# NEO9M.net
KiCad netlist of a schematic drawn in Altium Designer
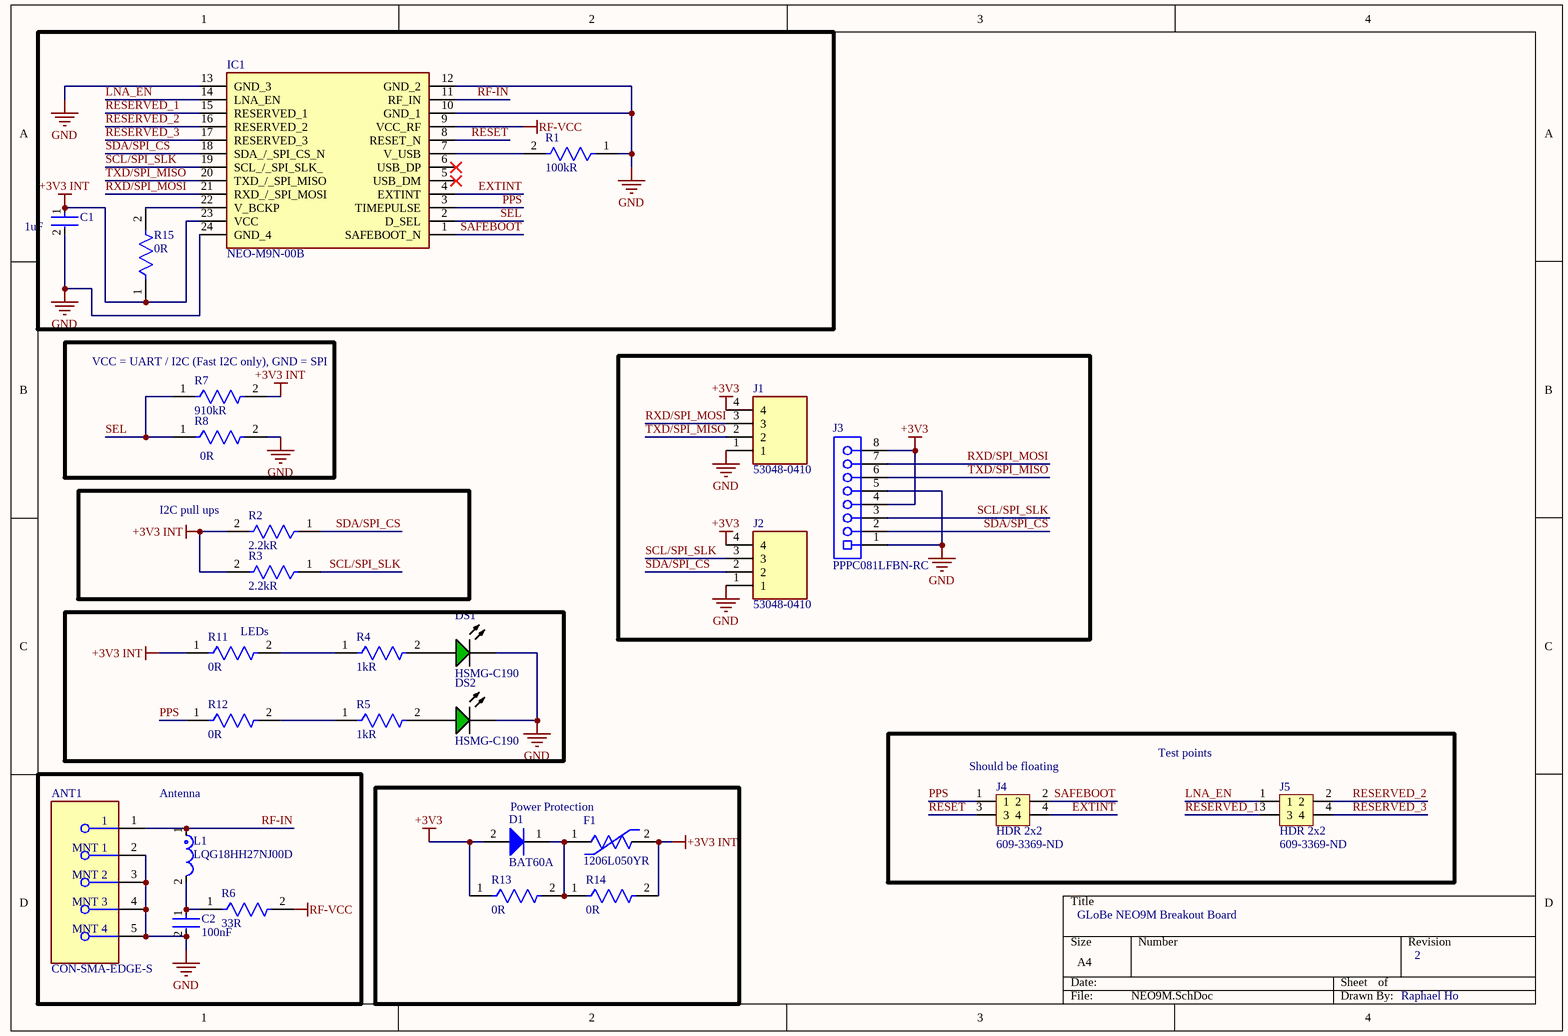
[diagram p0: NEO9M.SchDoc]

(export (version "E")
  (design (tool "Eeschema 10.0.6"))
  (components
    (comp (ref "ANT1")
      (value "CON-SMA-EDGE-S")
      (footprint "FP-CON-SMA-EDGE-S-MFG")
      (description "CONN SMA JACK STR EDGE MNT")
      (fields
        (field (name "OCTOPART") "https://octopart.com/con-sma-edge-s-rf+solutions-70967450")
        (field (name "MANUFACTURER") "RF Solutions Ltd.")
      )
      (libsource (lib "Altium Content Vault") (part "a163d97a771fcdd2fd1f1a9264c171f"))
    )
    (comp (ref "C1")
      (value "1uF")
      (footprint "FP-GCM188-0_1-IPC_B")
      (description "Ceramic Capacitor for Automotive 1uF  ±10% 16VDC X7R 0603 Paper T/R")
      (fields (field (name "VOLTAGE") "16V") (field (name "TOLERANCE") "10%"))
      (libsource (lib "Altium Content Vault") (part "02cd4be3c70576c341d710602a673aa"))
    )
    (comp (ref "C2")
      (value "100nF")
      (footprint "FP-GCM188-0_1-IPC_A")
      (description "CAP CER 0.1UF 50V X7R 0603")
      (fields (field (name "TOLERANCE") "10%"))
      (libsource (lib "Altium Content Vault") (part "b4654b650e69147ec39a6b967a45e02"))
    )
    (comp (ref "D1")
      (value "BAT60A")
      (footprint "INF-SOD323_V")
      (description "Silicon Schottky Diode, -55 to 85 degC, SOD323, Reel, Green")
      (fields (field (name "MANUFACTURER") "Infineon"))
      (libsource (lib "Altium Content Vault") (part "INF-D_K1A2-2"))
    )
    (comp (ref "DS1")
      (value "HSMG-C190")
      (footprint "AVAG-HSMX-C190_V")
      (description "Chip LED, Green, 2.2 V, -40 to 85 degC, 2-Pin SMD, RoHS, Tape and Reel")
      (libsource (lib "Altium Content Vault") (part "LED-GREEN-AK-2"))
    )
    (comp (ref "DS2")
      (value "HSMG-C190")
      (footprint "AVAG-HSMX-C190_V")
      (description "Chip LED, Green, 2.2 V, -40 to 85 degC, 2-Pin SMD, RoHS, Tape and Reel")
      (libsource (lib "Altium Content Vault") (part "LED-GREEN-AK-2"))
    )
    (comp (ref "F1")
      (value "1206L050YR")
      (footprint "FP-1206L050YR-MFG")
      (description "PTC RESET FUSE 6V 500MA 1206")
      (libsource (lib "Altium Content Vault") (part "fdf083d5f6389a9a1c4e51137f46658"))
    )
    (comp (ref "IC1")
      (value "NEO-M9N-00B")
      (footprint "SamacSys:NEOM9N00B")
      (description "Integrated Circuit")
      (fields (field (name "MOUSER PART NUMBER") "377-NEO-M9N-00B"))
      (libsource (lib "*") (part "NEO-M9N-00B"))
    )
    (comp (ref "J1")
      (value "53048-0410")
      (footprint "SamacSys:530480410")
      (description "Connector")
      (fields (field (name "MOUSER PART NUMBER") "538-53048-0410"))
      (libsource (lib "*") (part "53048-0410"))
    )
    (comp (ref "J2")
      (value "53048-0410")
      (footprint "SamacSys:530480410")
      (description "Connector")
      (fields (field (name "MOUSER PART NUMBER") "538-53048-0410"))
      (libsource (lib "*") (part "53048-0410"))
    )
    (comp (ref "J3")
      (value "PPPC081LFBN-RC")
      (footprint "SLIN-PPPC081LFBN-RC_V")
      (fields (field (name "MANUFACTURER") "Sullins"))
      (libsource (lib "CubeSat Team") (part "CN-1P-F-R8"))
    )
    (comp (ref "J4")
      (value "HDR 2x2")
      (footprint "HDR_2x2_2.54mm")
      (description "CONN HEADER VERT 4POS 2.54MM")
      (fields
        (field (name "MANUFACTURER") "Amphenol FCI")
        (field (name "MANUFACTURER PART NUMBER") "68602-204HLF")
        (field (name "SUPPLIER PART NUMBER 1") "609-3369-ND")
      )
      (libsource (lib "Male_Header_2x2_2.54mm") (part "68602-204HLF"))
    )
    (comp (ref "J5")
      (value "HDR 2x2")
      (footprint "HDR_2x2_2.54mm")
      (description "CONN HEADER VERT 4POS 2.54MM")
      (fields
        (field (name "MANUFACTURER") "Amphenol FCI")
        (field (name "MANUFACTURER PART NUMBER") "68602-204HLF")
        (field (name "SUPPLIER PART NUMBER 1") "609-3369-ND")
      )
      (libsource (lib "Male_Header_2x2_2.54mm") (part "68602-204HLF"))
    )
    (comp (ref "L1")
      (value "LQG18HH27NJ00D")
      (footprint "FP-LQG18HH_00-IPC_C")
      (description "Multilayer type Inductor for Automotive 27nH ±5% 0.54Ω 500mA 0603")
      (libsource (lib "Altium Content Vault") (part "4cc4b267dca4c8e51f7102f422741d8"))
    )
    (comp (ref "R1")
      (value "100kR")
      (footprint "FP-AC0603-MFG")
      (description "RES 100kΩ 5.00% 0.1W 0603")
      (fields (field (name "TOLERANCE") "5%"))
      (libsource (lib "Altium Content Vault") (part "1029c3af85768c4190bb7ad29bc67b5"))
    )
    (comp (ref "R2")
      (value "2.2kR")
      (footprint "FP-AC0603-IPC_B")
      (description "RES 2.2kΩ 5.00% 0.1W 0603")
      (fields (field (name "TOLERANCE") "5%"))
      (libsource (lib "Altium Content Vault") (part "1029c3af85768c4190bb7ad29bc67b5"))
    )
    (comp (ref "R3")
      (value "2.2kR")
      (footprint "FP-AC0603-IPC_B")
      (description "RES 2.2kΩ 5.00% 0.1W 0603")
      (fields (field (name "TOLERANCE") "5%"))
      (libsource (lib "Altium Content Vault") (part "1029c3af85768c4190bb7ad29bc67b5"))
    )
    (comp (ref "R4")
      (value "1kR")
      (footprint "FP-AC0603-IPC_A")
      (description "RES 1kΩ 1.00% 0.1W 0603")
      (fields (field (name "TOLERANCE") "1%"))
      (libsource (lib "Altium Content Vault") (part "1029c3af85768c4190bb7ad29bc67b5"))
    )
    (comp (ref "R5")
      (value "1kR")
      (footprint "FP-AC0603-IPC_A")
      (description "RES 1kΩ 1.00% 0.1W 0603")
      (fields (field (name "TOLERANCE") "1%"))
      (libsource (lib "Altium Content Vault") (part "1029c3af85768c4190bb7ad29bc67b5"))
    )
    (comp (ref "R6")
      (value "33R")
      (footprint "FP-AC0603-IPC_C")
      (description "RES 33Ω 0.50% 0.1W 0603")
      (libsource (lib "Altium Content Vault") (part "1029c3af85768c4190bb7ad29bc67b5"))
    )
    (comp (ref "R7")
      (value "910kR")
      (footprint "FP-AC0603-IPC_B")
      (description "RES 910KΩ 1.00% 0.1W 0603")
      (fields (field (name "TOLERANCE") "1%"))
      (libsource (lib "Altium Content Vault") (part "1029c3af85768c4190bb7ad29bc67b5"))
    )
    (comp (ref "R8")
      (value "0R")
      (footprint "FP-AC0603-IPC_A")
      (description "RES 0Ω 0.00% 0.1W 0603")
      (fields (field (name "TOLERANCE") "5%"))
      (libsource (lib "Altium Content Vault") (part "1029c3af85768c4190bb7ad29bc67b5"))
    )
    (comp (ref "R11")
      (value "0R")
      (footprint "FP-AC0603-IPC_A")
      (description "RES 0Ω 0.00% 0.1W 0603")
      (fields (field (name "TOLERANCE") "5%"))
      (libsource (lib "Altium Content Vault") (part "1029c3af85768c4190bb7ad29bc67b5"))
    )
    (comp (ref "R12")
      (value "0R")
      (footprint "FP-AC0603-IPC_A")
      (description "RES 0Ω 0.00% 0.1W 0603")
      (fields (field (name "TOLERANCE") "5%"))
      (libsource (lib "Altium Content Vault") (part "1029c3af85768c4190bb7ad29bc67b5"))
    )
    (comp (ref "R13")
      (value "0R")
      (footprint "FP-AC0603-IPC_A")
      (description "RES 0Ω 0.00% 0.1W 0603")
      (fields (field (name "TOLERANCE") "5%"))
      (libsource (lib "Altium Content Vault") (part "1029c3af85768c4190bb7ad29bc67b5"))
    )
    (comp (ref "R14")
      (value "0R")
      (footprint "FP-AC0603-IPC_A")
      (description "RES 0Ω 0.00% 0.1W 0603")
      (fields (field (name "TOLERANCE") "5%"))
      (libsource (lib "Altium Content Vault") (part "1029c3af85768c4190bb7ad29bc67b5"))
    )
    (comp (ref "R15")
      (value "0R")
      (footprint "FP-AC0603-IPC_A")
      (description "RES 0Ω 0.00% 0.1W 0603")
      (fields (field (name "TOLERANCE") "5%"))
      (libsource (lib "Altium Content Vault") (part "1029c3af85768c4190bb7ad29bc67b5"))
    )
  )
  (nets
    (net (code "1") (name "+3V3") (class "Default")
      (node (ref "D1") (pin "2") (pinfunction "A_2") (pintype "passive"))
      (node (ref "J1") (pin "4") (pinfunction "4_4") (pintype "passive"))
      (node (ref "J2") (pin "4") (pinfunction "4_4") (pintype "passive"))
      (node (ref "J3") (pin "4") (pinfunction "4_4") (pintype "passive"))
      (node (ref "J3") (pin "8") (pinfunction "8_8") (pintype "passive"))
      (node (ref "R13") (pin "1") (pinfunction "1_1") (pintype "passive"))
    )
    (net (code "2") (name "+3V3 INT") (class "Default")
      (node (ref "C1") (pin "1") (pinfunction "1_1") (pintype "passive"))
      (node (ref "F1") (pin "2") (pinfunction "2_2") (pintype "passive"))
      (node (ref "IC1") (pin "23") (pinfunction "VCC_23") (pintype "passive"))
      (node (ref "R11") (pin "1") (pinfunction "1_1") (pintype "passive"))
      (node (ref "R14") (pin "2") (pinfunction "2_2") (pintype "passive"))
      (node (ref "R15") (pin "1") (pinfunction "1_1") (pintype "passive"))
      (node (ref "R2") (pin "2") (pinfunction "2_2") (pintype "passive"))
      (node (ref "R3") (pin "2") (pinfunction "2_2") (pintype "passive"))
      (node (ref "R7") (pin "2") (pinfunction "2_2") (pintype "passive"))
    )
    (net (code "3") (name "/EXTINT") (class "Default")
      (node (ref "IC1") (pin "4") (pinfunction "EXTINT_4") (pintype "passive"))
      (node (ref "J4") (pin "4") (pinfunction "4_4") (pintype "passive"))
    )
    (net (code "4") (name "/LNA_EN") (class "Default")
      (node (ref "IC1") (pin "14") (pinfunction "LNA_EN_14") (pintype "passive"))
      (node (ref "J5") (pin "1") (pinfunction "1_1") (pintype "passive"))
    )
    (net (code "5") (name "/PPS") (class "Default")
      (node (ref "IC1") (pin "3") (pinfunction "TIMEPULSE_3") (pintype "passive"))
      (node (ref "J4") (pin "1") (pinfunction "1_1") (pintype "passive"))
      (node (ref "R12") (pin "1") (pinfunction "1_1") (pintype "passive"))
    )
    (net (code "6") (name "/RESERVED_1") (class "Default")
      (node (ref "IC1") (pin "15") (pinfunction "RESERVED_1_15") (pintype "passive"))
      (node (ref "J5") (pin "3") (pinfunction "3_3") (pintype "passive"))
    )
    (net (code "7") (name "/RESERVED_2") (class "Default")
      (node (ref "IC1") (pin "16") (pinfunction "RESERVED_2_16") (pintype "passive"))
      (node (ref "J5") (pin "2") (pinfunction "2_2") (pintype "passive"))
    )
    (net (code "8") (name "/RESERVED_3") (class "Default")
      (node (ref "IC1") (pin "17") (pinfunction "RESERVED_3_17") (pintype "passive"))
      (node (ref "J5") (pin "4") (pinfunction "4_4") (pintype "passive"))
    )
    (net (code "9") (name "/RESET") (class "Default")
      (node (ref "IC1") (pin "8") (pinfunction "RESET_N_8") (pintype "passive"))
      (node (ref "J4") (pin "3") (pinfunction "3_3") (pintype "passive"))
    )
    (net (code "10") (name "/RF-IN") (class "Default")
      (node (ref "ANT1") (pin "1") (pinfunction "1_1") (pintype "passive"))
      (node (ref "IC1") (pin "11") (pinfunction "RF_IN_11") (pintype "passive"))
      (node (ref "L1") (pin "1") (pinfunction "1_1") (pintype "passive"))
    )
    (net (code "11") (name "/RXD{slash}SPI_MOSI") (class "Default")
      (node (ref "IC1") (pin "21") (pinfunction "RXD_/_SPI_MOSI_21") (pintype "passive"))
      (node (ref "J1") (pin "3") (pinfunction "3_3") (pintype "passive"))
      (node (ref "J3") (pin "7") (pinfunction "7_7") (pintype "passive"))
    )
    (net (code "12") (name "/SAFEBOOT") (class "Default")
      (node (ref "IC1") (pin "1") (pinfunction "SAFEBOOT_N_1") (pintype "passive"))
      (node (ref "J4") (pin "2") (pinfunction "2_2") (pintype "passive"))
    )
    (net (code "13") (name "/SCL{slash}SPI_SLK") (class "Default")
      (node (ref "IC1") (pin "19") (pinfunction "SCL_/_SPI_SLK__19") (pintype "passive"))
      (node (ref "J2") (pin "3") (pinfunction "3_3") (pintype "passive"))
      (node (ref "J3") (pin "3") (pinfunction "3_3") (pintype "passive"))
      (node (ref "R3") (pin "1") (pinfunction "1_1") (pintype "passive"))
    )
    (net (code "14") (name "/SDA{slash}SPI_CS") (class "Default")
      (node (ref "IC1") (pin "18") (pinfunction "SDA_/_SPI_CS_N_18") (pintype "passive"))
      (node (ref "J2") (pin "2") (pinfunction "2_2") (pintype "passive"))
      (node (ref "J3") (pin "2") (pinfunction "2_2") (pintype "passive"))
      (node (ref "R2") (pin "1") (pinfunction "1_1") (pintype "passive"))
    )
    (net (code "15") (name "/SEL") (class "Default")
      (node (ref "IC1") (pin "2") (pinfunction "D_SEL_2") (pintype "passive"))
      (node (ref "R7") (pin "1") (pinfunction "1_1") (pintype "passive"))
      (node (ref "R8") (pin "1") (pinfunction "1_1") (pintype "passive"))
    )
    (net (code "16") (name "/TXD{slash}SPI_MISO") (class "Default")
      (node (ref "IC1") (pin "20") (pinfunction "TXD_/_SPI_MISO_20") (pintype "passive"))
      (node (ref "J1") (pin "2") (pinfunction "2_2") (pintype "passive"))
      (node (ref "J3") (pin "6") (pinfunction "6_6") (pintype "passive"))
    )
    (net (code "17") (name "GND") (class "Default")
      (node (ref "ANT1") (pin "2") (pinfunction "MNT_1_2") (pintype "passive"))
      (node (ref "ANT1") (pin "3") (pinfunction "MNT_2_3") (pintype "passive"))
      (node (ref "ANT1") (pin "4") (pinfunction "MNT_3_4") (pintype "passive"))
      (node (ref "ANT1") (pin "5") (pinfunction "MNT_4_5") (pintype "passive"))
      (node (ref "C1") (pin "2") (pinfunction "2_2") (pintype "passive"))
      (node (ref "C2") (pin "2") (pinfunction "2_2") (pintype "passive"))
      (node (ref "DS1") (pin "2") (pinfunction "K_2") (pintype "passive"))
      (node (ref "DS2") (pin "2") (pinfunction "K_2") (pintype "passive"))
      (node (ref "IC1") (pin "10") (pinfunction "GND_1_10") (pintype "passive"))
      (node (ref "IC1") (pin "12") (pinfunction "GND_2_12") (pintype "passive"))
      (node (ref "IC1") (pin "13") (pinfunction "GND_3_13") (pintype "passive"))
      (node (ref "IC1") (pin "24") (pinfunction "GND_4_24") (pintype "passive"))
      (node (ref "J1") (pin "1") (pinfunction "1_1") (pintype "passive"))
      (node (ref "J2") (pin "1") (pinfunction "1_1") (pintype "passive"))
      (node (ref "J3") (pin "1") (pinfunction "1_1") (pintype "passive"))
      (node (ref "J3") (pin "5") (pinfunction "5_5") (pintype "passive"))
      (node (ref "R1") (pin "1") (pinfunction "1_1") (pintype "passive"))
      (node (ref "R8") (pin "2") (pinfunction "2_2") (pintype "passive"))
    )
    (net (code "18") (name "Net-(C2-Pad1)") (class "Default")
      (node (ref "C2") (pin "1") (pinfunction "1_1") (pintype "passive"))
      (node (ref "L1") (pin "2") (pinfunction "2_2") (pintype "passive"))
      (node (ref "R6") (pin "1") (pinfunction "1_1") (pintype "passive"))
    )
    (net (code "19") (name "Net-(D1-K)") (class "Default")
      (node (ref "D1") (pin "1") (pinfunction "K_1") (pintype "passive"))
      (node (ref "F1") (pin "1") (pinfunction "1_1") (pintype "passive"))
      (node (ref "R13") (pin "2") (pinfunction "2_2") (pintype "passive"))
      (node (ref "R14") (pin "1") (pinfunction "1_1") (pintype "passive"))
    )
    (net (code "20") (name "Net-(DS1-A)") (class "Default")
      (node (ref "DS1") (pin "1") (pinfunction "A_1") (pintype "passive"))
      (node (ref "R4") (pin "2") (pinfunction "2_2") (pintype "passive"))
    )
    (net (code "21") (name "Net-(DS2-A)") (class "Default")
      (node (ref "DS2") (pin "1") (pinfunction "A_1") (pintype "passive"))
      (node (ref "R5") (pin "2") (pinfunction "2_2") (pintype "passive"))
    )
    (net (code "22") (name "Net-(IC1-V_BCKP)") (class "Default")
      (node (ref "IC1") (pin "22") (pinfunction "V_BCKP_22") (pintype "passive"))
      (node (ref "R15") (pin "2") (pinfunction "2_2") (pintype "passive"))
    )
    (net (code "23") (name "Net-(IC1-V_USB)") (class "Default")
      (node (ref "IC1") (pin "7") (pinfunction "V_USB_7") (pintype "passive"))
      (node (ref "R1") (pin "2") (pinfunction "2_2") (pintype "passive"))
    )
    (net (code "24") (name "Net-(R11-Pad2)") (class "Default")
      (node (ref "R11") (pin "2") (pinfunction "2_2") (pintype "passive"))
      (node (ref "R4") (pin "1") (pinfunction "1_1") (pintype "passive"))
    )
    (net (code "25") (name "Net-(R12-Pad2)") (class "Default")
      (node (ref "R12") (pin "2") (pinfunction "2_2") (pintype "passive"))
      (node (ref "R5") (pin "1") (pinfunction "1_1") (pintype "passive"))
    )
    (net (code "26") (name "RF-VCC") (class "Default")
      (node (ref "IC1") (pin "9") (pinfunction "VCC_RF_9") (pintype "passive"))
      (node (ref "R6") (pin "2") (pinfunction "2_2") (pintype "passive"))
    )
    (net (code "27") (name "unconnected-(IC1-USB_DM-Pad5)") (class "Default")
      (node (ref "IC1") (pin "5") (pinfunction "USB_DM_5") (pintype "passive+no_connect"))
    )
    (net (code "28") (name "unconnected-(IC1-USB_DP-Pad6)") (class "Default")
      (node (ref "IC1") (pin "6") (pinfunction "USB_DP_6") (pintype "passive+no_connect"))
    )
  )
)
